# frontpanel.net
KiCad netlist of a schematic drawn in EAGLE
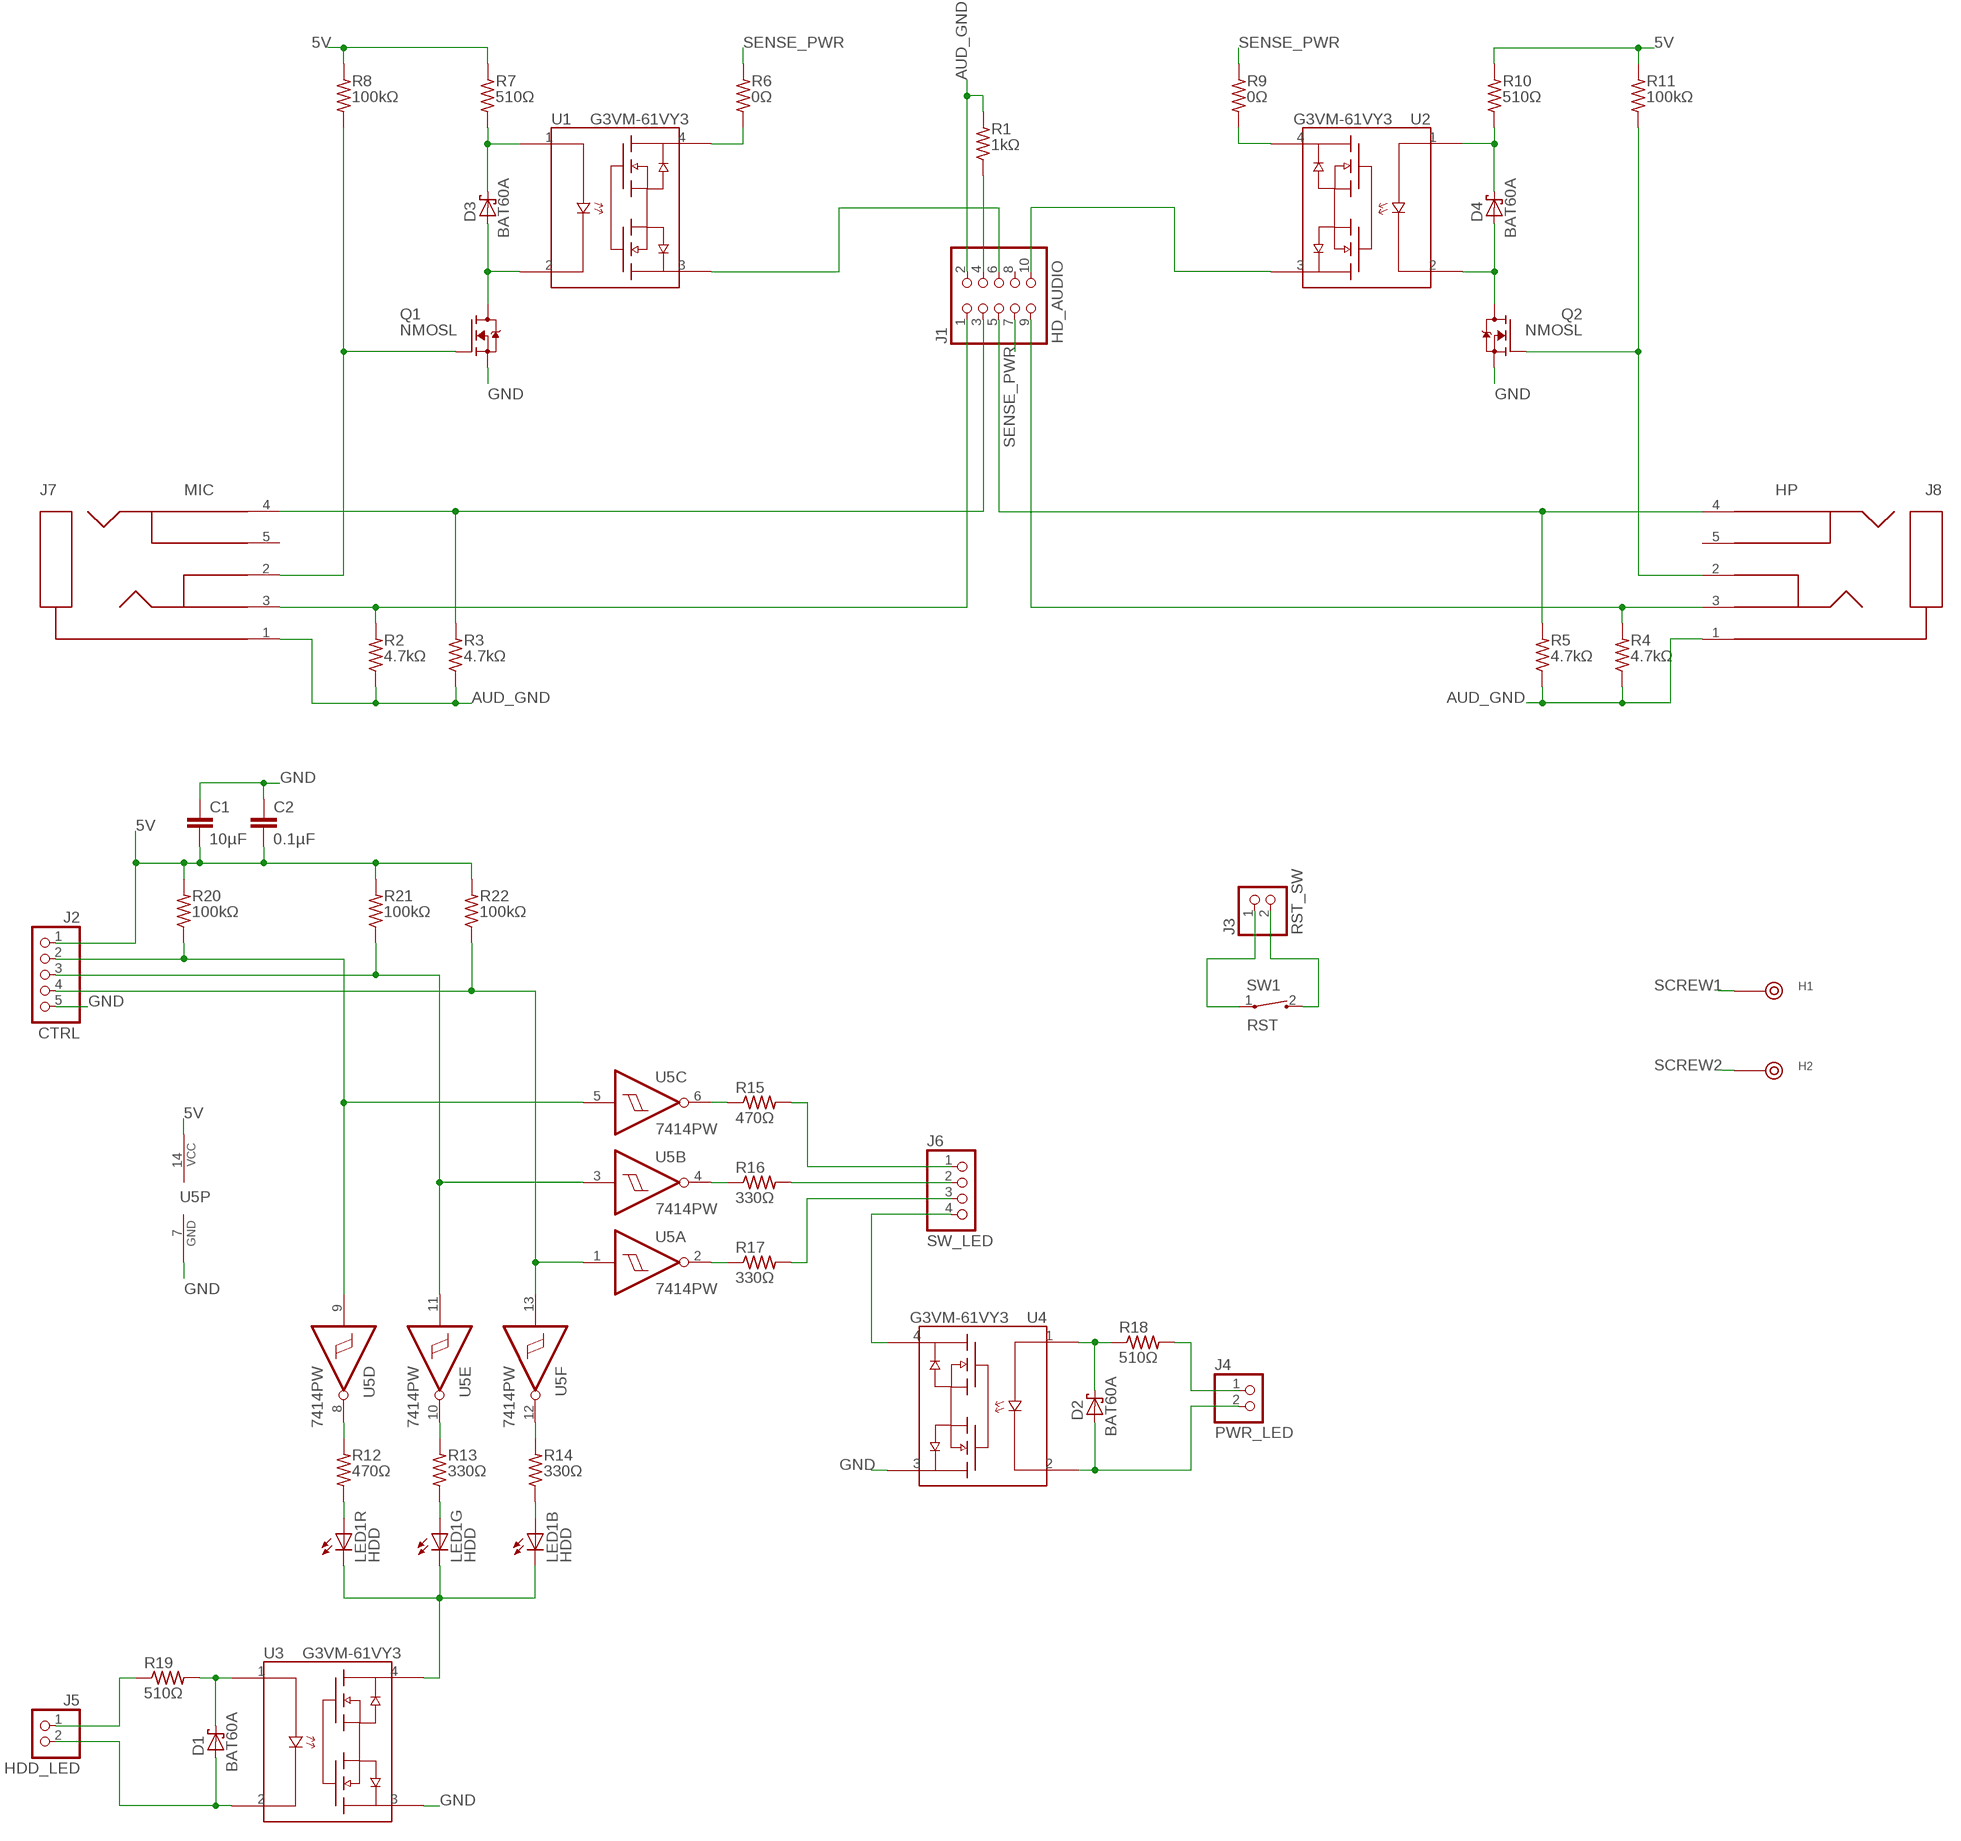
[diagram p0: schematic, sheet 1]

(export (version "E")
  (design (tool "Eeschema 10.0.6"))
  (components
    (comp (ref "C1")
      (value "10µF")
      (footprint "eagle-import:C0805")
      (libsource (lib "eagle-import") (part "C-EUC0805"))
    )
    (comp (ref "C2")
      (value "0.1µF")
      (footprint "eagle-import:C0603")
      (libsource (lib "eagle-import") (part "C-EUC0603"))
    )
    (comp (ref "D1")
      (value "BAT60A")
      (footprint "eagle-import:SOD323")
      (libsource (lib "eagle-import") (part "SOD323-SCHOTTKY"))
    )
    (comp (ref "D2")
      (value "BAT60A")
      (footprint "eagle-import:SOD323")
      (libsource (lib "eagle-import") (part "SOD323-SCHOTTKY"))
    )
    (comp (ref "D3")
      (value "BAT60A")
      (footprint "eagle-import:SOD323")
      (libsource (lib "eagle-import") (part "SOD323-SCHOTTKY"))
    )
    (comp (ref "D4")
      (value "BAT60A")
      (footprint "eagle-import:SOD323")
      (libsource (lib "eagle-import") (part "SOD323-SCHOTTKY"))
    )
    (comp (ref "H1")
      (value "7466313R")
      (footprint "eagle-import:7466313R")
      (libsource (lib "eagle-import") (part "7466313R"))
    )
    (comp (ref "H2")
      (value "7466313R")
      (footprint "eagle-import:7466313R")
      (libsource (lib "eagle-import") (part "7466313R"))
    )
    (comp (ref "J1")
      (value "HD_AUDIO")
      (footprint "eagle-import:2X05")
      (libsource (lib "eagle-import") (part "PINHD-2X5"))
    )
    (comp (ref "J2")
      (value "CTRL")
      (footprint "eagle-import:1X05")
      (libsource (lib "eagle-import") (part "PINHD-1X5"))
    )
    (comp (ref "J3")
      (value "RST_SW")
      (footprint "eagle-import:1X02")
      (libsource (lib "eagle-import") (part "PINHD-1X2"))
    )
    (comp (ref "J4")
      (value "PWR_LED")
      (footprint "eagle-import:1X02")
      (libsource (lib "eagle-import") (part "PINHD-1X2"))
    )
    (comp (ref "J5")
      (value "HDD_LED")
      (footprint "eagle-import:1X02")
      (libsource (lib "eagle-import") (part "PINHD-1X2"))
    )
    (comp (ref "J6")
      (value "SW_LED")
      (footprint "eagle-import:1X04")
      (libsource (lib "eagle-import") (part "PINHD-1X4"))
    )
    (comp (ref "J7")
      (value "MIC")
      (footprint "eagle-import:ACJS-MV35-5")
      (libsource (lib "eagle-import") (part "ACJS-V35-5-M"))
    )
    (comp (ref "J8")
      (value "HP")
      (footprint "eagle-import:ACJS-MV35-5")
      (libsource (lib "eagle-import") (part "ACJS-V35-5-M"))
    )
    (comp (ref "LED1")
      (value "HDD")
      (footprint "eagle-import:PLCC-6")
      (libsource (lib "eagle-import") (part "PLCC-6-RGBLED"))
    )
    (comp (ref "Q1")
      (value "NMOSL")
      (footprint "eagle-import:SOT23")
      (libsource (lib "eagle-import") (part "SOT23-N-MOSFET"))
    )
    (comp (ref "Q2")
      (value "NMOSL")
      (footprint "eagle-import:SOT23")
      (libsource (lib "eagle-import") (part "SOT23-N-MOSFET"))
    )
    (comp (ref "R1")
      (value "1kΩ")
      (footprint "eagle-import:R0603")
      (libsource (lib "eagle-import") (part "R-US_R0603"))
    )
    (comp (ref "R2")
      (value "4.7kΩ")
      (footprint "eagle-import:R0603")
      (libsource (lib "eagle-import") (part "R-US_R0603"))
    )
    (comp (ref "R3")
      (value "4.7kΩ")
      (footprint "eagle-import:R0603")
      (libsource (lib "eagle-import") (part "R-US_R0603"))
    )
    (comp (ref "R4")
      (value "4.7kΩ")
      (footprint "eagle-import:R0603")
      (libsource (lib "eagle-import") (part "R-US_R0603"))
    )
    (comp (ref "R5")
      (value "4.7kΩ")
      (footprint "eagle-import:R0603")
      (libsource (lib "eagle-import") (part "R-US_R0603"))
    )
    (comp (ref "R6")
      (value "0Ω")
      (footprint "eagle-import:R0603")
      (libsource (lib "eagle-import") (part "R-US_R0603"))
    )
    (comp (ref "R7")
      (value "510Ω")
      (footprint "eagle-import:R0603")
      (libsource (lib "eagle-import") (part "R-US_R0603"))
    )
    (comp (ref "R8")
      (value "100kΩ")
      (footprint "eagle-import:R0603")
      (libsource (lib "eagle-import") (part "R-US_R0603"))
    )
    (comp (ref "R9")
      (value "0Ω")
      (footprint "eagle-import:R0603")
      (libsource (lib "eagle-import") (part "R-US_R0603"))
    )
    (comp (ref "R10")
      (value "510Ω")
      (footprint "eagle-import:R0603")
      (libsource (lib "eagle-import") (part "R-US_R0603"))
    )
    (comp (ref "R11")
      (value "100kΩ")
      (footprint "eagle-import:R0603")
      (libsource (lib "eagle-import") (part "R-US_R0603"))
    )
    (comp (ref "R12")
      (value "470Ω")
      (footprint "eagle-import:R0603")
      (libsource (lib "eagle-import") (part "R-US_R0603"))
    )
    (comp (ref "R13")
      (value "330Ω")
      (footprint "eagle-import:R0603")
      (libsource (lib "eagle-import") (part "R-US_R0603"))
    )
    (comp (ref "R14")
      (value "330Ω")
      (footprint "eagle-import:R0603")
      (libsource (lib "eagle-import") (part "R-US_R0603"))
    )
    (comp (ref "R15")
      (value "470Ω")
      (footprint "eagle-import:R0603")
      (libsource (lib "eagle-import") (part "R-US_R0603"))
    )
    (comp (ref "R16")
      (value "330Ω")
      (footprint "eagle-import:R0603")
      (libsource (lib "eagle-import") (part "R-US_R0603"))
    )
    (comp (ref "R17")
      (value "330Ω")
      (footprint "eagle-import:R0603")
      (libsource (lib "eagle-import") (part "R-US_R0603"))
    )
    (comp (ref "R18")
      (value "510Ω")
      (footprint "eagle-import:R0603")
      (libsource (lib "eagle-import") (part "R-US_R0603"))
    )
    (comp (ref "R19")
      (value "510Ω")
      (footprint "eagle-import:R0603")
      (libsource (lib "eagle-import") (part "R-US_R0603"))
    )
    (comp (ref "R20")
      (value "100kΩ")
      (footprint "eagle-import:R0603")
      (libsource (lib "eagle-import") (part "R-US_R0603"))
    )
    (comp (ref "R21")
      (value "100kΩ")
      (footprint "eagle-import:R0603")
      (libsource (lib "eagle-import") (part "R-US_R0603"))
    )
    (comp (ref "R22")
      (value "100kΩ")
      (footprint "eagle-import:R0603")
      (libsource (lib "eagle-import") (part "R-US_R0603"))
    )
    (comp (ref "SW1")
      (value "RST")
      (footprint "eagle-import:TLS-_J-LFS")
      (libsource (lib "eagle-import") (part "TLS-J-LFSA-070"))
    )
    (comp (ref "U1")
      (value "G3VM-61VY3")
      (footprint "eagle-import:SOP-4")
      (libsource (lib "eagle-import") (part "SOP-4-SSR"))
    )
    (comp (ref "U2")
      (value "G3VM-61VY3")
      (footprint "eagle-import:SOP-4")
      (libsource (lib "eagle-import") (part "SOP-4-SSR"))
    )
    (comp (ref "U3")
      (value "G3VM-61VY3")
      (footprint "eagle-import:SOP-4")
      (libsource (lib "eagle-import") (part "SOP-4-SSR"))
    )
    (comp (ref "U4")
      (value "G3VM-61VY3")
      (footprint "eagle-import:SOP-4")
      (libsource (lib "eagle-import") (part "SOP-4-SSR"))
    )
    (comp (ref "U5")
      (value "7414PW")
      (footprint "eagle-import:TSSOP14")
      (libsource (lib "eagle-import") (part "7414PW"))
    )
  )
  (nets
    (net (code "1") (name "/5V") (class "Default")
      (node (ref "C1") (pin "2") (pinfunction "2_2") (pintype "passive"))
      (node (ref "C2") (pin "2") (pinfunction "2_2") (pintype "passive"))
      (node (ref "J2") (pin "1") (pinfunction "1_1") (pintype "passive"))
      (node (ref "R10") (pin "2") (pinfunction "2_2") (pintype "passive"))
      (node (ref "R11") (pin "2") (pinfunction "2_2") (pintype "passive"))
      (node (ref "R20") (pin "2") (pinfunction "2_2") (pintype "passive"))
      (node (ref "R21") (pin "2") (pinfunction "2_2") (pintype "passive"))
      (node (ref "R22") (pin "2") (pinfunction "2_2") (pintype "passive"))
      (node (ref "R7") (pin "2") (pinfunction "2_2") (pintype "passive"))
      (node (ref "R8") (pin "2") (pinfunction "2_2") (pintype "passive"))
      (node (ref "U5") (pin "14") (pinfunction "VCC_14") (pintype "power_in"))
    )
    (net (code "2") (name "/AUD_GND") (class "Default")
      (node (ref "J1") (pin "2") (pinfunction "2_2") (pintype "passive"))
      (node (ref "J7") (pin "1") (pinfunction "S_1") (pintype "bidirectional"))
      (node (ref "J8") (pin "1") (pinfunction "S_1") (pintype "bidirectional"))
      (node (ref "R1") (pin "2") (pinfunction "2_2") (pintype "passive"))
      (node (ref "R2") (pin "1") (pinfunction "1_1") (pintype "passive"))
      (node (ref "R3") (pin "1") (pinfunction "1_1") (pintype "passive"))
      (node (ref "R4") (pin "1") (pinfunction "1_1") (pintype "passive"))
      (node (ref "R5") (pin "1") (pinfunction "1_1") (pintype "passive"))
    )
    (net (code "3") (name "/GND") (class "Default")
      (node (ref "C1") (pin "1") (pinfunction "1_1") (pintype "passive"))
      (node (ref "C2") (pin "1") (pinfunction "1_1") (pintype "passive"))
      (node (ref "J2") (pin "5") (pinfunction "5_5") (pintype "passive"))
      (node (ref "Q1") (pin "2") (pinfunction "S_2") (pintype "passive"))
      (node (ref "Q2") (pin "2") (pinfunction "S_2") (pintype "passive"))
      (node (ref "U3") (pin "3") (pinfunction "1_3") (pintype "passive"))
      (node (ref "U4") (pin "3") (pinfunction "1_3") (pintype "passive"))
      (node (ref "U5") (pin "7") (pinfunction "GND_7") (pintype "power_in"))
    )
    (net (code "4") (name "/SCREW1") (class "Default")
      (node (ref "H1") (pin "H1") (pinfunction "P$1_H1") (pintype "bidirectional"))
      (node (ref "H1") (pin "H2") (pinfunction "P$1_H2") (pintype "bidirectional"))
      (node (ref "H1") (pin "P") (pinfunction "P$1_P") (pintype "bidirectional"))
    )
    (net (code "5") (name "/SCREW2") (class "Default")
      (node (ref "H2") (pin "H1") (pinfunction "P$1_H1") (pintype "bidirectional"))
      (node (ref "H2") (pin "H2") (pinfunction "P$1_H2") (pintype "bidirectional"))
      (node (ref "H2") (pin "P") (pinfunction "P$1_P") (pintype "bidirectional"))
    )
    (net (code "6") (name "/SENSE_PWR") (class "Default")
      (node (ref "J1") (pin "7") (pinfunction "7_7") (pintype "passive"))
      (node (ref "R6") (pin "2") (pinfunction "2_2") (pintype "passive"))
      (node (ref "R9") (pin "2") (pinfunction "2_2") (pintype "passive"))
    )
    (net (code "7") (name "Net-(D1-A)") (class "Default")
      (node (ref "D1") (pin "2") (pinfunction "A_2") (pintype "passive"))
      (node (ref "J5") (pin "2") (pinfunction "2_2") (pintype "passive"))
      (node (ref "U3") (pin "2") (pinfunction "K_2") (pintype "passive"))
    )
    (net (code "8") (name "Net-(D1-C)") (class "Default")
      (node (ref "D1") (pin "1") (pinfunction "C_1") (pintype "passive"))
      (node (ref "R19") (pin "2") (pinfunction "2_2") (pintype "passive"))
      (node (ref "U3") (pin "1") (pinfunction "A_1") (pintype "passive"))
    )
    (net (code "9") (name "Net-(D2-A)") (class "Default")
      (node (ref "D2") (pin "2") (pinfunction "A_2") (pintype "passive"))
      (node (ref "J4") (pin "2") (pinfunction "2_2") (pintype "passive"))
      (node (ref "U4") (pin "2") (pinfunction "K_2") (pintype "passive"))
    )
    (net (code "10") (name "Net-(D2-C)") (class "Default")
      (node (ref "D2") (pin "1") (pinfunction "C_1") (pintype "passive"))
      (node (ref "R18") (pin "1") (pinfunction "1_1") (pintype "passive"))
      (node (ref "U4") (pin "1") (pinfunction "A_1") (pintype "passive"))
    )
    (net (code "11") (name "Net-(D3-A)") (class "Default")
      (node (ref "D3") (pin "2") (pinfunction "A_2") (pintype "passive"))
      (node (ref "Q1") (pin "3") (pinfunction "D_3") (pintype "passive"))
      (node (ref "U1") (pin "2") (pinfunction "K_2") (pintype "passive"))
    )
    (net (code "12") (name "Net-(D3-C)") (class "Default")
      (node (ref "D3") (pin "1") (pinfunction "C_1") (pintype "passive"))
      (node (ref "R7") (pin "1") (pinfunction "1_1") (pintype "passive"))
      (node (ref "U1") (pin "1") (pinfunction "A_1") (pintype "passive"))
    )
    (net (code "13") (name "Net-(D4-A)") (class "Default")
      (node (ref "D4") (pin "2") (pinfunction "A_2") (pintype "passive"))
      (node (ref "Q2") (pin "3") (pinfunction "D_3") (pintype "passive"))
      (node (ref "U2") (pin "2") (pinfunction "K_2") (pintype "passive"))
    )
    (net (code "14") (name "Net-(D4-C)") (class "Default")
      (node (ref "D4") (pin "1") (pinfunction "C_1") (pintype "passive"))
      (node (ref "R10") (pin "1") (pinfunction "1_1") (pintype "passive"))
      (node (ref "U2") (pin "1") (pinfunction "A_1") (pintype "passive"))
    )
    (net (code "15") (name "Net-(J1-Pad4)") (class "Default")
      (node (ref "J1") (pin "4") (pinfunction "4_4") (pintype "passive"))
      (node (ref "R1") (pin "1") (pinfunction "1_1") (pintype "passive"))
    )
    (net (code "16") (name "Net-(J3-Pad1)") (class "Default")
      (node (ref "J3") (pin "1") (pinfunction "1_1") (pintype "passive"))
      (node (ref "SW1") (pin "1") (pinfunction "1_1") (pintype "passive"))
    )
    (net (code "17") (name "Net-(J3-Pad2)") (class "Default")
      (node (ref "J3") (pin "2") (pinfunction "2_2") (pintype "passive"))
      (node (ref "SW1") (pin "2") (pinfunction "2_2") (pintype "passive"))
    )
    (net (code "18") (name "Net-(J4-Pad1)") (class "Default")
      (node (ref "J4") (pin "1") (pinfunction "1_1") (pintype "passive"))
      (node (ref "R18") (pin "2") (pinfunction "2_2") (pintype "passive"))
    )
    (net (code "19") (name "Net-(J5-Pad1)") (class "Default")
      (node (ref "J5") (pin "1") (pinfunction "1_1") (pintype "passive"))
      (node (ref "R19") (pin "1") (pinfunction "1_1") (pintype "passive"))
    )
    (net (code "20") (name "Net-(J6-Pad1)") (class "Default")
      (node (ref "J6") (pin "1") (pinfunction "1_1") (pintype "passive"))
      (node (ref "R15") (pin "2") (pinfunction "2_2") (pintype "passive"))
    )
    (net (code "21") (name "Net-(J6-Pad2)") (class "Default")
      (node (ref "J6") (pin "2") (pinfunction "2_2") (pintype "passive"))
      (node (ref "R16") (pin "2") (pinfunction "2_2") (pintype "passive"))
    )
    (net (code "22") (name "Net-(J6-Pad3)") (class "Default")
      (node (ref "J6") (pin "3") (pinfunction "3_3") (pintype "passive"))
      (node (ref "R17") (pin "2") (pinfunction "2_2") (pintype "passive"))
    )
    (net (code "23") (name "Net-(J7-R)") (class "Default")
      (node (ref "J1") (pin "3") (pinfunction "3_3") (pintype "passive"))
      (node (ref "J7") (pin "4") (pinfunction "R_4") (pintype "bidirectional"))
      (node (ref "R3") (pin "2") (pinfunction "2_2") (pintype "passive"))
    )
    (net (code "24") (name "Net-(J7-T)") (class "Default")
      (node (ref "J1") (pin "1") (pinfunction "1_1") (pintype "passive"))
      (node (ref "J7") (pin "3") (pinfunction "T_3") (pintype "bidirectional"))
      (node (ref "R2") (pin "2") (pinfunction "2_2") (pintype "passive"))
    )
    (net (code "25") (name "Net-(J7-T-RETURN)") (class "Default")
      (node (ref "J7") (pin "2") (pinfunction "T-RETURN_2") (pintype "bidirectional"))
      (node (ref "Q1") (pin "1") (pinfunction "G_1") (pintype "passive"))
      (node (ref "R8") (pin "1") (pinfunction "1_1") (pintype "passive"))
    )
    (net (code "26") (name "Net-(J8-R)") (class "Default")
      (node (ref "J1") (pin "5") (pinfunction "5_5") (pintype "passive"))
      (node (ref "J8") (pin "4") (pinfunction "R_4") (pintype "bidirectional"))
      (node (ref "R5") (pin "2") (pinfunction "2_2") (pintype "passive"))
    )
    (net (code "27") (name "Net-(J8-T)") (class "Default")
      (node (ref "J1") (pin "9") (pinfunction "9_9") (pintype "passive"))
      (node (ref "J8") (pin "3") (pinfunction "T_3") (pintype "bidirectional"))
      (node (ref "R4") (pin "2") (pinfunction "2_2") (pintype "passive"))
    )
    (net (code "28") (name "Net-(J8-T-RETURN)") (class "Default")
      (node (ref "J8") (pin "2") (pinfunction "T-RETURN_2") (pintype "bidirectional"))
      (node (ref "Q2") (pin "1") (pinfunction "G_1") (pintype "passive"))
      (node (ref "R11") (pin "1") (pinfunction "1_1") (pintype "passive"))
    )
    (net (code "29") (name "Net-(LED1A-A)") (class "Default")
      (node (ref "LED1") (pin "5") (pinfunction "A_5") (pintype "passive"))
      (node (ref "R14") (pin "1") (pinfunction "1_1") (pintype "passive"))
    )
    (net (code "30") (name "Net-(LED1A-C)") (class "Default")
      (node (ref "LED1") (pin "2") (pinfunction "C_2") (pintype "passive"))
      (node (ref "LED1") (pin "4") (pinfunction "C_4") (pintype "passive"))
      (node (ref "LED1") (pin "6") (pinfunction "C_6") (pintype "passive"))
      (node (ref "U3") (pin "4") (pinfunction "2_4") (pintype "passive"))
    )
    (net (code "31") (name "Net-(LED1B-A)") (class "Default")
      (node (ref "LED1") (pin "3") (pinfunction "A_3") (pintype "passive"))
      (node (ref "R13") (pin "1") (pinfunction "1_1") (pintype "passive"))
    )
    (net (code "32") (name "Net-(LED1C-A)") (class "Default")
      (node (ref "LED1") (pin "1") (pinfunction "A_1") (pintype "passive"))
      (node (ref "R12") (pin "1") (pinfunction "1_1") (pintype "passive"))
    )
    (net (code "33") (name "Net-(U1-1)") (class "Default")
      (node (ref "J1") (pin "6") (pinfunction "6_6") (pintype "passive"))
      (node (ref "U1") (pin "3") (pinfunction "1_3") (pintype "passive"))
    )
    (net (code "34") (name "Net-(U1-2)") (class "Default")
      (node (ref "R6") (pin "1") (pinfunction "1_1") (pintype "passive"))
      (node (ref "U1") (pin "4") (pinfunction "2_4") (pintype "passive"))
    )
    (net (code "35") (name "Net-(U2-1)") (class "Default")
      (node (ref "J1") (pin "10") (pinfunction "10_10") (pintype "passive"))
      (node (ref "U2") (pin "3") (pinfunction "1_3") (pintype "passive"))
    )
    (net (code "36") (name "Net-(U2-2)") (class "Default")
      (node (ref "R9") (pin "1") (pinfunction "1_1") (pintype "passive"))
      (node (ref "U2") (pin "4") (pinfunction "2_4") (pintype "passive"))
    )
    (net (code "37") (name "Net-(U4-2)") (class "Default")
      (node (ref "J6") (pin "4") (pinfunction "4_4") (pintype "passive"))
      (node (ref "U4") (pin "4") (pinfunction "2_4") (pintype "passive"))
    )
    (net (code "38") (name "Net-(U5A-I)") (class "Default")
      (node (ref "J2") (pin "4") (pinfunction "4_4") (pintype "passive"))
      (node (ref "R22") (pin "1") (pinfunction "1_1") (pintype "passive"))
      (node (ref "U5") (pin "1") (pinfunction "I_1") (pintype "input"))
      (node (ref "U5") (pin "13") (pinfunction "I_13") (pintype "input"))
    )
    (net (code "39") (name "Net-(U5A-O)") (class "Default")
      (node (ref "R17") (pin "1") (pinfunction "1_1") (pintype "passive"))
      (node (ref "U5") (pin "2") (pinfunction "O_2") (pintype "output"))
    )
    (net (code "40") (name "Net-(U5B-I)") (class "Default")
      (node (ref "J2") (pin "3") (pinfunction "3_3") (pintype "passive"))
      (node (ref "R21") (pin "1") (pinfunction "1_1") (pintype "passive"))
      (node (ref "U5") (pin "11") (pinfunction "I_11") (pintype "input"))
      (node (ref "U5") (pin "3") (pinfunction "I_3") (pintype "input"))
    )
    (net (code "41") (name "Net-(U5B-O)") (class "Default")
      (node (ref "R16") (pin "1") (pinfunction "1_1") (pintype "passive"))
      (node (ref "U5") (pin "4") (pinfunction "O_4") (pintype "output"))
    )
    (net (code "42") (name "Net-(U5C-I)") (class "Default")
      (node (ref "J2") (pin "2") (pinfunction "2_2") (pintype "passive"))
      (node (ref "R20") (pin "1") (pinfunction "1_1") (pintype "passive"))
      (node (ref "U5") (pin "5") (pinfunction "I_5") (pintype "input"))
      (node (ref "U5") (pin "9") (pinfunction "I_9") (pintype "input"))
    )
    (net (code "43") (name "Net-(U5C-O)") (class "Default")
      (node (ref "R15") (pin "1") (pinfunction "1_1") (pintype "passive"))
      (node (ref "U5") (pin "6") (pinfunction "O_6") (pintype "output"))
    )
    (net (code "44") (name "Net-(U5D-O)") (class "Default")
      (node (ref "R12") (pin "2") (pinfunction "2_2") (pintype "passive"))
      (node (ref "U5") (pin "8") (pinfunction "O_8") (pintype "output"))
    )
    (net (code "45") (name "Net-(U5E-O)") (class "Default")
      (node (ref "R13") (pin "2") (pinfunction "2_2") (pintype "passive"))
      (node (ref "U5") (pin "10") (pinfunction "O_10") (pintype "output"))
    )
    (net (code "46") (name "Net-(U5F-O)") (class "Default")
      (node (ref "R14") (pin "2") (pinfunction "2_2") (pintype "passive"))
      (node (ref "U5") (pin "12") (pinfunction "O_12") (pintype "output"))
    )
    (net (code "47") (name "unconnected-(J1-Pad8)") (class "Default")
      (node (ref "J1") (pin "8") (pinfunction "8_8") (pintype "passive"))
    )
    (net (code "48") (name "unconnected-(J7-R-RETURN-Pad5)") (class "Default")
      (node (ref "J7") (pin "5") (pinfunction "R-RETURN_5") (pintype "bidirectional"))
    )
    (net (code "49") (name "unconnected-(J8-R-RETURN-Pad5)") (class "Default")
      (node (ref "J8") (pin "5") (pinfunction "R-RETURN_5") (pintype "bidirectional"))
    )
  )
)
